# Programming.net
KiCad netlist of a schematic drawn in Altium Designer
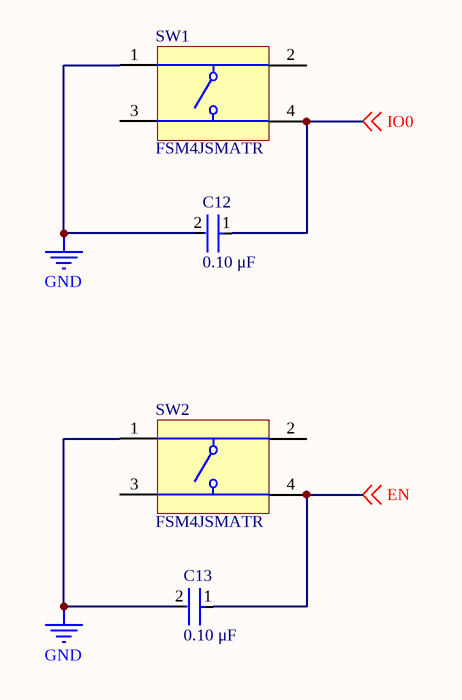
[diagram p0: Programming.SchDoc]

(export (version "E")
  (design (tool "Eeschema 10.0.6"))
  (components
    (comp (ref "C12")
      (value "C0603C104K5RACTU")
      (footprint "FP-C0603C-CF-MFG")
      (description "CAP CER 0.1UF 50V X7R 0603")
      (fields
        (field (name "TOLERANCE") "0.1")
        (field (name "MANUFACTURER") "KEMET")
        (field (name "CAPACITANCE") "0.10 μF")
      )
      (libsource (lib "Altium Content Vault") (part "b4654b650e69147ec39a6b967a45e02"))
    )
    (comp (ref "C13")
      (value "C0603C104K5RACTU")
      (footprint "FP-C0603C-CF-MFG")
      (description "CAP CER 0.1UF 50V X7R 0603")
      (fields
        (field (name "TOLERANCE") "0.1")
        (field (name "MANUFACTURER") "KEMET")
        (field (name "CAPACITANCE") "0.10 μF")
      )
      (libsource (lib "Altium Content Vault") (part "b4654b650e69147ec39a6b967a45e02"))
    )
    (comp (ref "SW1")
      (value "FSM4JSMATR")
      (footprint "TECO-FSM4JSMATR_V")
      (description "Micro Miniature Push Button Switch FSM JSM, 50 mA, -35 to 85 degC, 4-Pin SMD, RoHS, Tape and Reel")
      (fields (field (name "MANUFACTURER") "TE Connectivity"))
      (libsource (lib "Altium Content Vault") (part "SW-SPST-4_A"))
    )
    (comp (ref "SW2")
      (value "FSM4JSMATR")
      (footprint "TECO-FSM4JSMATR_V")
      (description "Micro Miniature Push Button Switch FSM JSM, 50 mA, -35 to 85 degC, 4-Pin SMD, RoHS, Tape and Reel")
      (fields (field (name "MANUFACTURER") "TE Connectivity"))
      (libsource (lib "Altium Content Vault") (part "SW-SPST-4_A"))
    )
  )
  (nets
    (net (code "1") (name "EN") (class "Default")
      (node (ref "C13") (pin "1") (pinfunction "1_1") (pintype "passive"))
      (node (ref "SW2") (pin "4") (pinfunction "4_4") (pintype "passive"))
    )
    (net (code "2") (name "GND") (class "Default")
      (node (ref "C12") (pin "2") (pinfunction "2_2") (pintype "passive"))
      (node (ref "C13") (pin "2") (pinfunction "2_2") (pintype "passive"))
      (node (ref "SW1") (pin "1") (pinfunction "1_1") (pintype "passive"))
      (node (ref "SW2") (pin "1") (pinfunction "1_1") (pintype "passive"))
    )
    (net (code "3") (name "IO0") (class "Default")
      (node (ref "C12") (pin "1") (pinfunction "1_1") (pintype "passive"))
      (node (ref "SW1") (pin "4") (pinfunction "4_4") (pintype "passive"))
    )
    (net (code "4") (name "unconnected-(SW1-Pad2)") (class "Default")
      (node (ref "SW1") (pin "2") (pinfunction "2_2") (pintype "passive"))
    )
    (net (code "5") (name "unconnected-(SW1-Pad3)") (class "Default")
      (node (ref "SW1") (pin "3") (pinfunction "3_3") (pintype "passive"))
    )
    (net (code "6") (name "unconnected-(SW2-Pad2)") (class "Default")
      (node (ref "SW2") (pin "2") (pinfunction "2_2") (pintype "passive"))
    )
    (net (code "7") (name "unconnected-(SW2-Pad3)") (class "Default")
      (node (ref "SW2") (pin "3") (pinfunction "3_3") (pintype "passive"))
    )
  )
)
